# bombclock_1_3.net
KiCad netlist of a schematic drawn in EAGLE
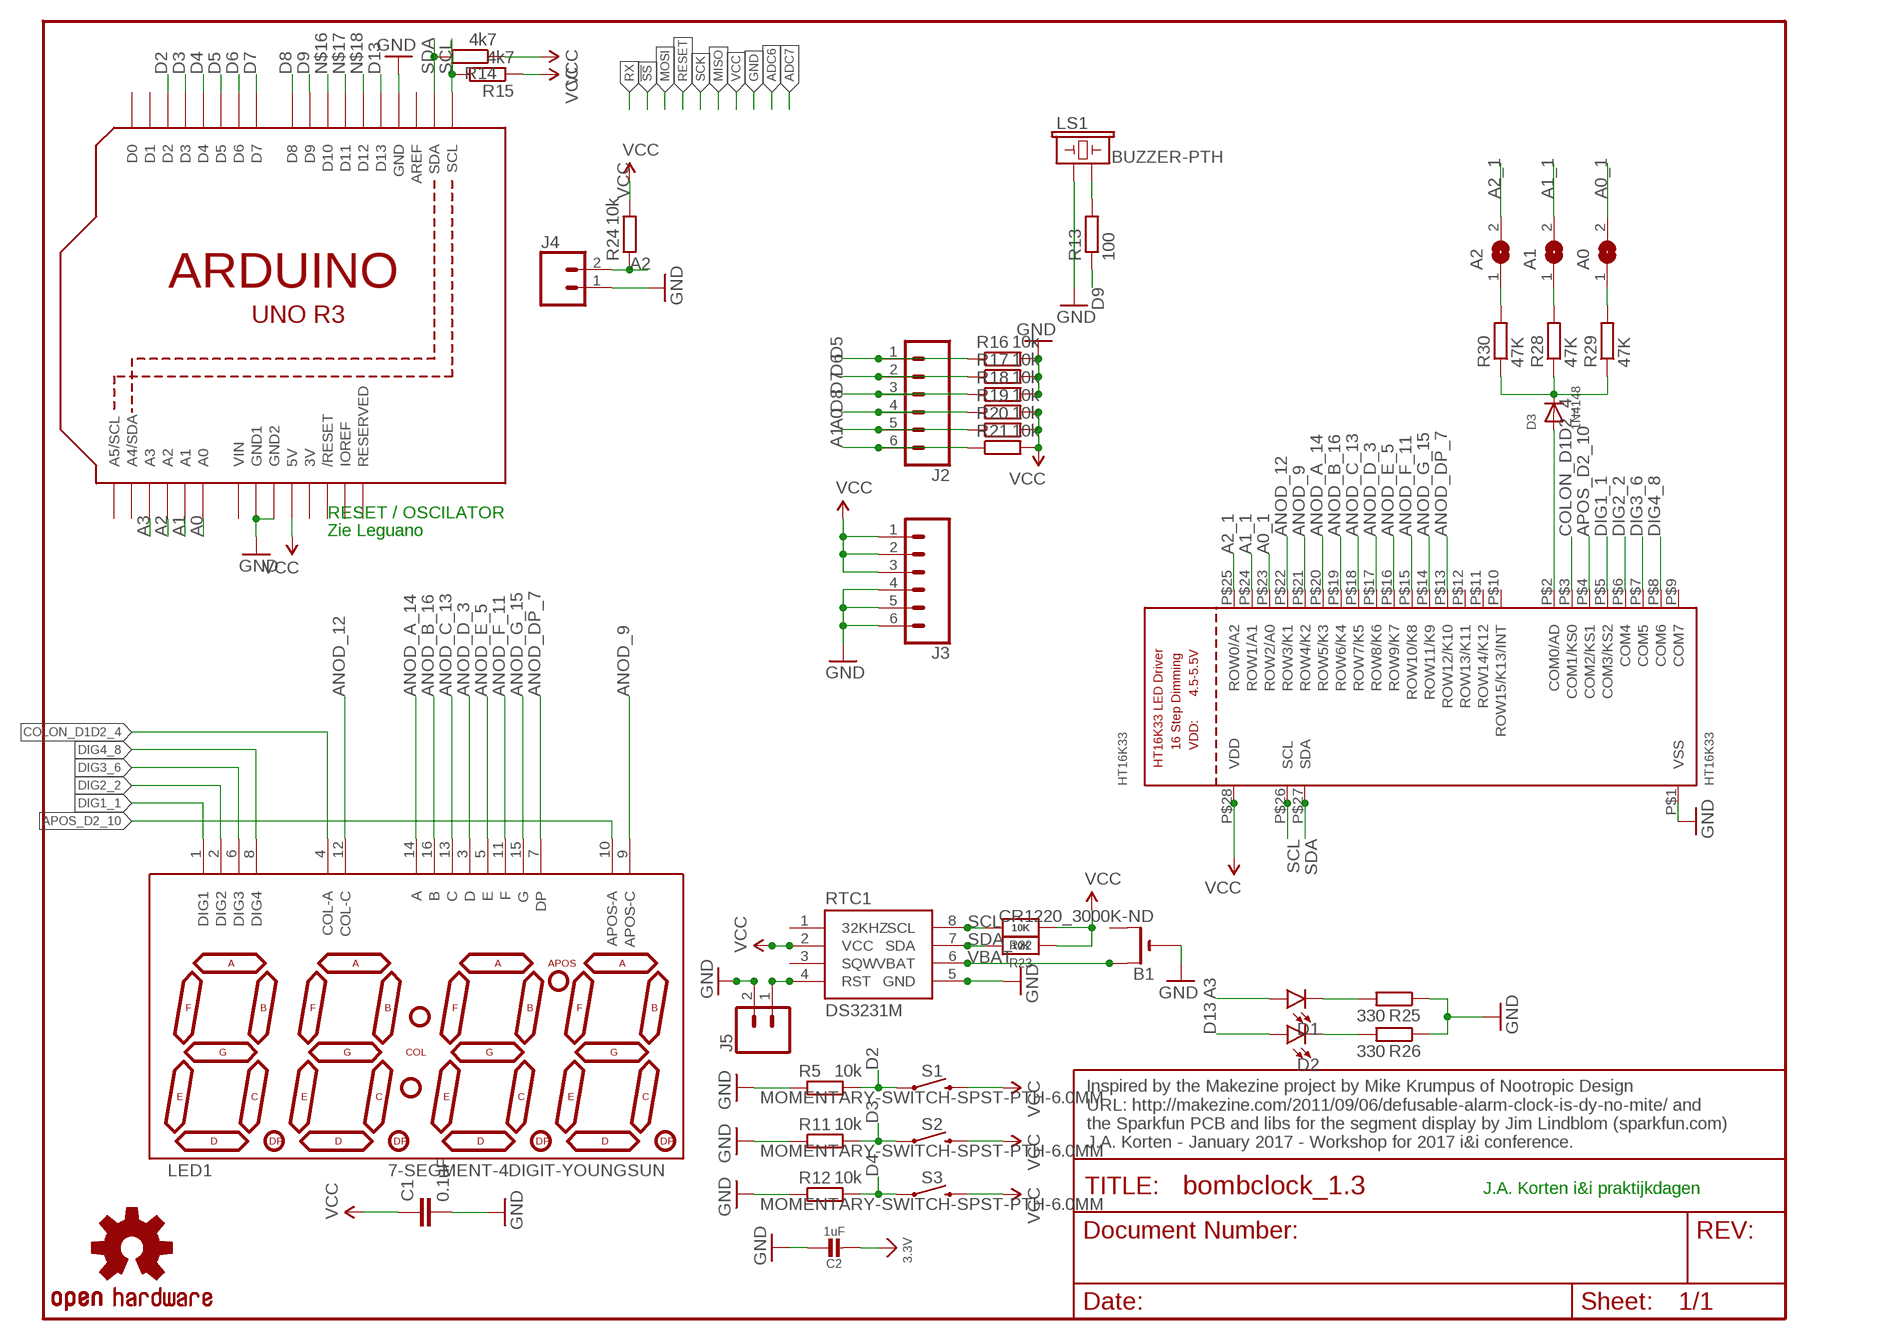
[diagram p0: schematic, sheet 1]

(export (version "E")
  (design (tool "Eeschema 10.0.6"))
  (components
    (comp (ref "A0")
      (value "SOLDERJUMPERREFLOW_NOPASTE")
      (footprint "eagle-import:SOLDERJUMPER_REFLOW_NOPASTE")
      (libsource (lib "eagle-import") (part "SOLDERJUMPERREFLOW_NOPASTE"))
    )
    (comp (ref "A1")
      (value "SOLDERJUMPERREFLOW_NOPASTE")
      (footprint "eagle-import:SOLDERJUMPER_REFLOW_NOPASTE")
      (libsource (lib "eagle-import") (part "SOLDERJUMPERREFLOW_NOPASTE"))
    )
    (comp (ref "A2")
      (value "SOLDERJUMPERREFLOW_NOPASTE")
      (footprint "eagle-import:SOLDERJUMPER_REFLOW_NOPASTE")
      (libsource (lib "eagle-import") (part "SOLDERJUMPERREFLOW_NOPASTE"))
    )
    (comp (ref "B1")
      (value "CR1220_3000K-ND")
      (footprint "eagle-import:CR1220-SMD")
      (libsource (lib "eagle-import") (part "CR1220SMT"))
    )
    (comp (ref "C1")
      (value "0.1uF")
      (footprint "eagle-import:0402-CAP")
      (libsource (lib "eagle-import") (part "CAP0402-CAP"))
    )
    (comp (ref "C2")
      (value "1uF")
      (footprint "eagle-import:0805-NO")
      (libsource (lib "eagle-import") (part "CAP_CERAMIC0805-NOOUTLINE"))
    )
    (comp (ref "D1")
      (value "LED5MM")
      (footprint "eagle-import:LED_5MM")
      (libsource (lib "eagle-import") (part "LED5MM"))
    )
    (comp (ref "D2")
      (value "LED5MM")
      (footprint "eagle-import:LED_5MM")
      (libsource (lib "eagle-import") (part "LED5MM"))
    )
    (comp (ref "D3")
      (value "1N4148")
      (footprint "eagle-import:SOD-323F")
      (libsource (lib "eagle-import") (part "DIODESOD-323F"))
    )
    (comp (ref "HT16K33")
      (value "HT16K33")
      (footprint "eagle-import:SOP28_300MIL")
      (libsource (lib "eagle-import") (part "HT16K33_SOP28"))
    )
    (comp (ref "J2")
      (value "CONN_06SILK_FEMALE_PTH")
      (footprint "eagle-import:1X06")
      (libsource (lib "eagle-import") (part "CONN_06SILK_FEMALE_PTH"))
    )
    (comp (ref "J3")
      (value "CONN_06SILK_FEMALE_PTH")
      (footprint "eagle-import:1X06")
      (libsource (lib "eagle-import") (part "CONN_06SILK_FEMALE_PTH"))
    )
    (comp (ref "J4")
      (value "CONN_02")
      (footprint "eagle-import:1X02")
      (libsource (lib "eagle-import") (part "CONN_02"))
    )
    (comp (ref "J5")
      (value "CONN_02")
      (footprint "eagle-import:1X02")
      (libsource (lib "eagle-import") (part "CONN_02"))
    )
    (comp (ref "LED1")
      (value "7-SEGMENT-4DIGIT-YOUNGSUN")
      (footprint "eagle-import:7-SEGMENT-4DIGIT-YOUNGSUN")
      (libsource (lib "eagle-import") (part "7-SEGMENT-4DIGIT-YOUNGSUN"))
    )
    (comp (ref "LS1")
      (value "BUZZER-PTH")
      (footprint "eagle-import:BUZZER-12MM")
      (libsource (lib "eagle-import") (part "BUZZER-PTH"))
    )
    (comp (ref "R5")
      (value "10k")
      (footprint "eagle-import:R0603")
      (libsource (lib "eagle-import") (part "R-EU_R0603"))
    )
    (comp (ref "R11")
      (value "10k")
      (footprint "eagle-import:R0603")
      (libsource (lib "eagle-import") (part "R-EU_R0603"))
    )
    (comp (ref "R12")
      (value "10k")
      (footprint "eagle-import:R0603")
      (libsource (lib "eagle-import") (part "R-EU_R0603"))
    )
    (comp (ref "R13")
      (value "100")
      (footprint "eagle-import:R0603")
      (libsource (lib "eagle-import") (part "R-EU_R0603"))
    )
    (comp (ref "R14")
      (value "4k7")
      (footprint "eagle-import:R0603")
      (libsource (lib "eagle-import") (part "R-EU_R0603"))
    )
    (comp (ref "R15")
      (value "4k7")
      (footprint "eagle-import:R0603")
      (libsource (lib "eagle-import") (part "R-EU_R0603"))
    )
    (comp (ref "R16")
      (value "10k")
      (footprint "eagle-import:R0603")
      (libsource (lib "eagle-import") (part "R-EU_R0603"))
    )
    (comp (ref "R17")
      (value "10k")
      (footprint "eagle-import:R0603")
      (libsource (lib "eagle-import") (part "R-EU_R0603"))
    )
    (comp (ref "R18")
      (value "10k")
      (footprint "eagle-import:R0603")
      (libsource (lib "eagle-import") (part "R-EU_R0603"))
    )
    (comp (ref "R19")
      (value "10k")
      (footprint "eagle-import:R0603")
      (libsource (lib "eagle-import") (part "R-EU_R0603"))
    )
    (comp (ref "R20")
      (value "10k")
      (footprint "eagle-import:R0603")
      (libsource (lib "eagle-import") (part "R-EU_R0603"))
    )
    (comp (ref "R21")
      (value "10k")
      (footprint "eagle-import:R0603")
      (libsource (lib "eagle-import") (part "R-EU_R0603"))
    )
    (comp (ref "R22")
      (value "10K")
      (footprint "eagle-import:0805-NO")
      (libsource (lib "eagle-import") (part "RESISTOR0805_NOOUTLINE"))
    )
    (comp (ref "R23")
      (value "10K")
      (footprint "eagle-import:0805-NO")
      (libsource (lib "eagle-import") (part "RESISTOR0805_NOOUTLINE"))
    )
    (comp (ref "R24")
      (value "10k")
      (footprint "eagle-import:R0603")
      (libsource (lib "eagle-import") (part "R-EU_R0603"))
    )
    (comp (ref "R25")
      (value "330")
      (footprint "eagle-import:R0603")
      (libsource (lib "eagle-import") (part "R-EU_R0603"))
    )
    (comp (ref "R26")
      (value "330")
      (footprint "eagle-import:R0603")
      (libsource (lib "eagle-import") (part "R-EU_R0603"))
    )
    (comp (ref "R28")
      (value "47K")
      (footprint "eagle-import:R0603")
      (libsource (lib "eagle-import") (part "resistor_R-EU_R0603"))
    )
    (comp (ref "R29")
      (value "47K")
      (footprint "eagle-import:R0603")
      (libsource (lib "eagle-import") (part "resistor_R-EU_R0603"))
    )
    (comp (ref "R30")
      (value "47K")
      (footprint "eagle-import:R0603")
      (libsource (lib "eagle-import") (part "resistor_R-EU_R0603"))
    )
    (comp (ref "RTC1")
      (value "DS3231M")
      (footprint "eagle-import:SO08")
      (libsource (lib "eagle-import") (part "DS3231M"))
    )
    (comp (ref "S1")
      (value "MOMENTARY-SWITCH-SPST-PTH-6.0MM")
      (footprint "eagle-import:TACTILE_SWITCH_PTH_6.0MM")
      (libsource (lib "eagle-import") (part "MOMENTARY-SWITCH-SPST-PTH-6.0MM"))
    )
    (comp (ref "S2")
      (value "MOMENTARY-SWITCH-SPST-PTH-6.0MM")
      (footprint "eagle-import:TACTILE_SWITCH_PTH_6.0MM")
      (libsource (lib "eagle-import") (part "MOMENTARY-SWITCH-SPST-PTH-6.0MM"))
    )
    (comp (ref "S3")
      (value "MOMENTARY-SWITCH-SPST-PTH-6.0MM")
      (footprint "eagle-import:TACTILE_SWITCH_PTH_6.0MM")
      (libsource (lib "eagle-import") (part "MOMENTARY-SWITCH-SPST-PTH-6.0MM"))
    )
    (comp (ref "U$4")
      (value "OSHW-LOGOS")
      (footprint "eagle-import:OSHW-LOGO-S")
      (libsource (lib "eagle-import") (part "OSHW-LOGOS"))
    )
    (comp (ref "U1")
      (value "ARDUINOR3-DIMENSION")
      (footprint "eagle-import:ARDUINOR3")
      (libsource (lib "eagle-import") (part "ARDUINOR3-DIMENSION"))
    )
  )
  (nets
    (net (code "1") (name "/3V") (class "Default")
      (node (ref "U1") (pin "3V") (pinfunction "3V_3V") (pintype "power_in"))
    )
    (net (code "2") (name "/A0") (class "Default")
      (node (ref "J2") (pin "5") (pinfunction "5_5") (pintype "passive"))
      (node (ref "R20") (pin "1") (pinfunction "1_1") (pintype "passive"))
      (node (ref "U1") (pin "A0") (pinfunction "A0_A0") (pintype "bidirectional"))
    )
    (net (code "3") (name "/A0_1") (class "Default")
      (node (ref "A0") (pin "2") (pinfunction "2_2") (pintype "passive"))
      (node (ref "HT16K33") (pin "P$23") (pinfunction "ROW2/A0_P$23") (pintype "bidirectional"))
    )
    (net (code "4") (name "/A1") (class "Default")
      (node (ref "J2") (pin "6") (pinfunction "6_6") (pintype "passive"))
      (node (ref "R21") (pin "1") (pinfunction "1_1") (pintype "passive"))
      (node (ref "U1") (pin "A1") (pinfunction "A1_A1") (pintype "bidirectional"))
    )
    (net (code "5") (name "/A1_1") (class "Default")
      (node (ref "A1") (pin "2") (pinfunction "2_2") (pintype "passive"))
      (node (ref "HT16K33") (pin "P$24") (pinfunction "ROW1/A1_P$24") (pintype "bidirectional"))
    )
    (net (code "6") (name "/A2") (class "Default")
      (node (ref "J4") (pin "2") (pinfunction "2_2") (pintype "passive"))
      (node (ref "R24") (pin "1") (pinfunction "1_1") (pintype "passive"))
      (node (ref "U1") (pin "A2") (pinfunction "A2_A2") (pintype "bidirectional"))
    )
    (net (code "7") (name "/A2_1") (class "Default")
      (node (ref "A2") (pin "2") (pinfunction "2_2") (pintype "passive"))
      (node (ref "HT16K33") (pin "P$25") (pinfunction "ROW0/A2_P$25") (pintype "bidirectional"))
    )
    (net (code "8") (name "/A3") (class "Default")
      (node (ref "D1") (pin "A") (pinfunction "A_A") (pintype "passive"))
      (node (ref "U1") (pin "A3") (pinfunction "A3_A3") (pintype "bidirectional"))
    )
    (net (code "9") (name "/ANOD_9") (class "Default")
      (node (ref "HT16K33") (pin "P$21") (pinfunction "ROW4/K2_P$21") (pintype "bidirectional"))
      (node (ref "LED1") (pin "9") (pinfunction "APOS-C_9") (pintype "bidirectional"))
    )
    (net (code "10") (name "/ANOD_12") (class "Default")
      (node (ref "HT16K33") (pin "P$22") (pinfunction "ROW3/K1_P$22") (pintype "bidirectional"))
      (node (ref "LED1") (pin "12") (pinfunction "COL-C_12") (pintype "bidirectional"))
    )
    (net (code "11") (name "/ANOD_A_14") (class "Default")
      (node (ref "HT16K33") (pin "P$20") (pinfunction "ROW5/K3_P$20") (pintype "bidirectional"))
      (node (ref "LED1") (pin "14") (pinfunction "A_14") (pintype "bidirectional"))
    )
    (net (code "12") (name "/ANOD_B_16") (class "Default")
      (node (ref "HT16K33") (pin "P$19") (pinfunction "ROW6/K4_P$19") (pintype "bidirectional"))
      (node (ref "LED1") (pin "16") (pinfunction "B_16") (pintype "bidirectional"))
    )
    (net (code "13") (name "/ANOD_C_13") (class "Default")
      (node (ref "HT16K33") (pin "P$18") (pinfunction "ROW7/K5_P$18") (pintype "bidirectional"))
      (node (ref "LED1") (pin "13") (pinfunction "C_13") (pintype "bidirectional"))
    )
    (net (code "14") (name "/ANOD_DP_7") (class "Default")
      (node (ref "HT16K33") (pin "P$13") (pinfunction "ROW12/K10_P$13") (pintype "bidirectional"))
      (node (ref "LED1") (pin "7") (pinfunction "DP_7") (pintype "bidirectional"))
    )
    (net (code "15") (name "/ANOD_D_3") (class "Default")
      (node (ref "HT16K33") (pin "P$17") (pinfunction "ROW8/K6_P$17") (pintype "bidirectional"))
      (node (ref "LED1") (pin "3") (pinfunction "D_3") (pintype "bidirectional"))
    )
    (net (code "16") (name "/ANOD_E_5") (class "Default")
      (node (ref "HT16K33") (pin "P$16") (pinfunction "ROW9/K7_P$16") (pintype "bidirectional"))
      (node (ref "LED1") (pin "5") (pinfunction "E_5") (pintype "bidirectional"))
    )
    (net (code "17") (name "/ANOD_F_11") (class "Default")
      (node (ref "HT16K33") (pin "P$15") (pinfunction "ROW10/K8_P$15") (pintype "bidirectional"))
      (node (ref "LED1") (pin "11") (pinfunction "F_11") (pintype "bidirectional"))
    )
    (net (code "18") (name "/ANOD_G_15") (class "Default")
      (node (ref "HT16K33") (pin "P$14") (pinfunction "ROW11/K9_P$14") (pintype "bidirectional"))
      (node (ref "LED1") (pin "15") (pinfunction "G_15") (pintype "bidirectional"))
    )
    (net (code "19") (name "/D2") (class "Default")
      (node (ref "R5") (pin "2") (pinfunction "2_2") (pintype "passive"))
      (node (ref "S1") (pin "1") (pinfunction "1_1") (pintype "passive"))
      (node (ref "U1") (pin "D2") (pinfunction "D2_D2") (pintype "bidirectional"))
    )
    (net (code "20") (name "/D3") (class "Default")
      (node (ref "R11") (pin "2") (pinfunction "2_2") (pintype "passive"))
      (node (ref "S2") (pin "1") (pinfunction "1_1") (pintype "passive"))
      (node (ref "U1") (pin "D3") (pinfunction "D3_D3") (pintype "bidirectional"))
    )
    (net (code "21") (name "/D4") (class "Default")
      (node (ref "R12") (pin "2") (pinfunction "2_2") (pintype "passive"))
      (node (ref "S3") (pin "1") (pinfunction "1_1") (pintype "passive"))
      (node (ref "U1") (pin "D4") (pinfunction "D4_D4") (pintype "bidirectional"))
    )
    (net (code "22") (name "/D5") (class "Default")
      (node (ref "J2") (pin "1") (pinfunction "1_1") (pintype "passive"))
      (node (ref "R16") (pin "1") (pinfunction "1_1") (pintype "passive"))
      (node (ref "U1") (pin "D5") (pinfunction "D5_D5") (pintype "bidirectional"))
    )
    (net (code "23") (name "/D6") (class "Default")
      (node (ref "J2") (pin "2") (pinfunction "2_2") (pintype "passive"))
      (node (ref "R17") (pin "1") (pinfunction "1_1") (pintype "passive"))
      (node (ref "U1") (pin "D6") (pinfunction "D6_D6") (pintype "bidirectional"))
    )
    (net (code "24") (name "/D7") (class "Default")
      (node (ref "J2") (pin "3") (pinfunction "3_3") (pintype "passive"))
      (node (ref "R18") (pin "1") (pinfunction "1_1") (pintype "passive"))
      (node (ref "U1") (pin "D7") (pinfunction "D7_D7") (pintype "bidirectional"))
    )
    (net (code "25") (name "/D8") (class "Default")
      (node (ref "J2") (pin "4") (pinfunction "4_4") (pintype "passive"))
      (node (ref "R19") (pin "1") (pinfunction "1_1") (pintype "passive"))
      (node (ref "U1") (pin "D8") (pinfunction "D8_D8") (pintype "bidirectional"))
    )
    (net (code "26") (name "/D9") (class "Default")
      (node (ref "R13") (pin "1") (pinfunction "1_1") (pintype "passive"))
      (node (ref "U1") (pin "D9") (pinfunction "D9_D9") (pintype "bidirectional"))
    )
    (net (code "27") (name "/D13") (class "Default")
      (node (ref "D2") (pin "A") (pinfunction "A_A") (pintype "passive"))
      (node (ref "U1") (pin "D13") (pinfunction "D13_D13") (pintype "bidirectional"))
    )
    (net (code "28") (name "/N$16") (class "Default")
      (node (ref "U1") (pin "D10") (pinfunction "D10_D10") (pintype "bidirectional"))
    )
    (net (code "29") (name "/N$17") (class "Default")
      (node (ref "U1") (pin "D11") (pinfunction "D11_D11") (pintype "bidirectional"))
    )
    (net (code "30") (name "/N$18") (class "Default")
      (node (ref "U1") (pin "D12") (pinfunction "D12_D12") (pintype "bidirectional"))
    )
    (net (code "31") (name "/SCL") (class "Default")
      (node (ref "HT16K33") (pin "P$26") (pinfunction "SCL_P$26") (pintype "bidirectional"))
      (node (ref "R15") (pin "2") (pinfunction "2_2") (pintype "passive"))
      (node (ref "R22") (pin "2") (pinfunction "2_2") (pintype "passive"))
      (node (ref "RTC1") (pin "8") (pinfunction "SCL_8") (pintype "bidirectional"))
      (node (ref "U1") (pin "SCL") (pinfunction "SCL_SCL") (pintype "bidirectional"))
    )
    (net (code "32") (name "/SDA") (class "Default")
      (node (ref "HT16K33") (pin "P$27") (pinfunction "SDA_P$27") (pintype "bidirectional"))
      (node (ref "R14") (pin "2") (pinfunction "2_2") (pintype "passive"))
      (node (ref "R23") (pin "2") (pinfunction "2_2") (pintype "passive"))
      (node (ref "RTC1") (pin "7") (pinfunction "SDA_7") (pintype "bidirectional"))
      (node (ref "U1") (pin "SDA") (pinfunction "SDA_SDA") (pintype "bidirectional"))
    )
    (net (code "33") (name "/VBAT") (class "Default")
      (node (ref "B1") (pin "+$1") (pinfunction "+_+$1") (pintype "passive"))
      (node (ref "RTC1") (pin "6") (pinfunction "VBAT_6") (pintype "power_in"))
    )
    (net (code "34") (name "/VIN") (class "Default")
      (node (ref "U1") (pin "VIN") (pinfunction "VIN_VIN") (pintype "power_in"))
    )
    (net (code "36") (name "3.3V") (class "Default")
      (node (ref "C2") (pin "2") (pinfunction "2_2") (pintype "passive"))
    )
    (net (code "39") (name "APOS_D2_10") (class "Default")
      (node (ref "HT16K33") (pin "P$4") (pinfunction "COM2/KS1_P$4") (pintype "bidirectional"))
      (node (ref "LED1") (pin "10") (pinfunction "APOS-A_10") (pintype "bidirectional"))
    )
    (net (code "40") (name "COLON_D1D2_4") (class "Default")
      (node (ref "HT16K33") (pin "P$3") (pinfunction "COM1/KS0_P$3") (pintype "bidirectional"))
      (node (ref "LED1") (pin "4") (pinfunction "COL-A_4") (pintype "bidirectional"))
    )
    (net (code "41") (name "DIG1_1") (class "Default")
      (node (ref "HT16K33") (pin "P$5") (pinfunction "COM3/KS2_P$5") (pintype "bidirectional"))
      (node (ref "LED1") (pin "1") (pinfunction "DIG1_1") (pintype "bidirectional"))
    )
    (net (code "42") (name "DIG2_2") (class "Default")
      (node (ref "HT16K33") (pin "P$6") (pinfunction "COM4_P$6") (pintype "bidirectional"))
      (node (ref "LED1") (pin "2") (pinfunction "DIG2_2") (pintype "bidirectional"))
    )
    (net (code "43") (name "DIG3_6") (class "Default")
      (node (ref "HT16K33") (pin "P$7") (pinfunction "COM5_P$7") (pintype "bidirectional"))
      (node (ref "LED1") (pin "6") (pinfunction "DIG3_6") (pintype "bidirectional"))
    )
    (net (code "44") (name "DIG4_8") (class "Default")
      (node (ref "HT16K33") (pin "P$8") (pinfunction "COM6_P$8") (pintype "bidirectional"))
      (node (ref "LED1") (pin "8") (pinfunction "DIG4_8") (pintype "bidirectional"))
    )
    (net (code "45") (name "GND") (class "Default")
      (node (ref "B1") (pin "-") (pinfunction "-_-") (pintype "passive"))
      (node (ref "C1") (pin "2") (pinfunction "2_2") (pintype "passive"))
      (node (ref "C2") (pin "1") (pinfunction "1_1") (pintype "passive"))
      (node (ref "HT16K33") (pin "P$1") (pinfunction "VSS_P$1") (pintype "bidirectional"))
      (node (ref "J3") (pin "4") (pinfunction "4_4") (pintype "passive"))
      (node (ref "J3") (pin "5") (pinfunction "5_5") (pintype "passive"))
      (node (ref "J3") (pin "6") (pinfunction "6_6") (pintype "passive"))
      (node (ref "J4") (pin "1") (pinfunction "1_1") (pintype "passive"))
      (node (ref "J5") (pin "2") (pinfunction "2_2") (pintype "passive"))
      (node (ref "LS1") (pin "+") (pinfunction "1_+") (pintype "passive"))
      (node (ref "R11") (pin "1") (pinfunction "1_1") (pintype "passive"))
      (node (ref "R12") (pin "1") (pinfunction "1_1") (pintype "passive"))
      (node (ref "R16") (pin "2") (pinfunction "2_2") (pintype "passive"))
      (node (ref "R17") (pin "2") (pinfunction "2_2") (pintype "passive"))
      (node (ref "R18") (pin "2") (pinfunction "2_2") (pintype "passive"))
      (node (ref "R25") (pin "1") (pinfunction "1_1") (pintype "passive"))
      (node (ref "R26") (pin "1") (pinfunction "1_1") (pintype "passive"))
      (node (ref "R5") (pin "1") (pinfunction "1_1") (pintype "passive"))
      (node (ref "RTC1") (pin "5") (pinfunction "GND_5") (pintype "power_in"))
      (node (ref "U1") (pin "GND") (pinfunction "GND_GND") (pintype "power_in"))
      (node (ref "U1") (pin "GND1") (pinfunction "GND1_GND1") (pintype "power_in"))
      (node (ref "U1") (pin "GND2") (pinfunction "GND2_GND2") (pintype "power_in"))
    )
    (net (code "48") (name "Net-(A0-Pad1)") (class "Default")
      (node (ref "A0") (pin "1") (pinfunction "1_1") (pintype "passive"))
      (node (ref "R29") (pin "2") (pinfunction "2_2") (pintype "passive"))
    )
    (net (code "49") (name "Net-(A1-Pad1)") (class "Default")
      (node (ref "A1") (pin "1") (pinfunction "1_1") (pintype "passive"))
      (node (ref "R28") (pin "2") (pinfunction "2_2") (pintype "passive"))
    )
    (net (code "50") (name "Net-(A2-Pad1)") (class "Default")
      (node (ref "A2") (pin "1") (pinfunction "1_1") (pintype "passive"))
      (node (ref "R30") (pin "2") (pinfunction "2_2") (pintype "passive"))
    )
    (net (code "51") (name "Net-(D1-C)") (class "Default")
      (node (ref "D1") (pin "K") (pinfunction "C_K") (pintype "passive"))
      (node (ref "R25") (pin "2") (pinfunction "2_2") (pintype "passive"))
    )
    (net (code "52") (name "Net-(D2-C)") (class "Default")
      (node (ref "D2") (pin "K") (pinfunction "C_K") (pintype "passive"))
      (node (ref "R26") (pin "2") (pinfunction "2_2") (pintype "passive"))
    )
    (net (code "53") (name "Net-(D3-PadC)") (class "Default")
      (node (ref "D3") (pin "C") (pinfunction "C_C") (pintype "passive"))
      (node (ref "R28") (pin "1") (pinfunction "1_1") (pintype "passive"))
      (node (ref "R29") (pin "1") (pinfunction "1_1") (pintype "passive"))
      (node (ref "R30") (pin "1") (pinfunction "1_1") (pintype "passive"))
    )
    (net (code "54") (name "Net-(HT16K33-COM0{slash}AD)") (class "Default")
      (node (ref "D3") (pin "A") (pinfunction "A_A") (pintype "passive"))
      (node (ref "HT16K33") (pin "P$2") (pinfunction "COM0/AD_P$2") (pintype "bidirectional"))
    )
    (net (code "55") (name "Net-(LS1-2)") (class "Default")
      (node (ref "LS1") (pin "-") (pinfunction "2_-") (pintype "passive"))
      (node (ref "R13") (pin "2") (pinfunction "2_2") (pintype "passive"))
    )
    (net (code "56") (name "Net-(RTC1-RST)") (class "Default")
      (node (ref "J5") (pin "1") (pinfunction "1_1") (pintype "passive"))
      (node (ref "RTC1") (pin "4") (pinfunction "RST_4") (pintype "bidirectional"))
    )
    (net (code "60") (name "VCC") (class "Default")
      (node (ref "C1") (pin "1") (pinfunction "1_1") (pintype "passive"))
      (node (ref "HT16K33") (pin "P$28") (pinfunction "VDD_P$28") (pintype "bidirectional"))
      (node (ref "J3") (pin "1") (pinfunction "1_1") (pintype "passive"))
      (node (ref "J3") (pin "2") (pinfunction "2_2") (pintype "passive"))
      (node (ref "J3") (pin "3") (pinfunction "3_3") (pintype "passive"))
      (node (ref "R14") (pin "1") (pinfunction "1_1") (pintype "passive"))
      (node (ref "R15") (pin "1") (pinfunction "1_1") (pintype "passive"))
      (node (ref "R19") (pin "2") (pinfunction "2_2") (pintype "passive"))
      (node (ref "R20") (pin "2") (pinfunction "2_2") (pintype "passive"))
      (node (ref "R21") (pin "2") (pinfunction "2_2") (pintype "passive"))
      (node (ref "R22") (pin "1") (pinfunction "1_1") (pintype "passive"))
      (node (ref "R23") (pin "1") (pinfunction "1_1") (pintype "passive"))
      (node (ref "R24") (pin "2") (pinfunction "2_2") (pintype "passive"))
      (node (ref "RTC1") (pin "2") (pinfunction "VCC_2") (pintype "power_in"))
      (node (ref "S1") (pin "3") (pinfunction "2_3") (pintype "passive"))
      (node (ref "S2") (pin "3") (pinfunction "2_3") (pintype "passive"))
      (node (ref "S3") (pin "3") (pinfunction "2_3") (pintype "passive"))
      (node (ref "U1") (pin "5V") (pinfunction "5V_5V") (pintype "power_in"))
    )
    (net (code "61") (name "unconnected-(B1-+1-Pad+$2)") (class "Default")
      (node (ref "B1") (pin "+$2") (pinfunction "+1_+$2") (pintype "passive"))
    )
    (net (code "62") (name "unconnected-(HT16K33-COM7-PadP$9)") (class "Default")
      (node (ref "HT16K33") (pin "P$9") (pinfunction "COM7_P$9") (pintype "bidirectional"))
    )
    (net (code "63") (name "unconnected-(HT16K33-ROW13{slash}K11-PadP$12)") (class "Default")
      (node (ref "HT16K33") (pin "P$12") (pinfunction "ROW13/K11_P$12") (pintype "bidirectional"))
    )
    (net (code "64") (name "unconnected-(HT16K33-ROW14{slash}K12-PadP$11)") (class "Default")
      (node (ref "HT16K33") (pin "P$11") (pinfunction "ROW14/K12_P$11") (pintype "bidirectional"))
    )
    (net (code "65") (name "unconnected-(HT16K33-ROW15{slash}K13{slash}INT-PadP$10)") (class "Default")
      (node (ref "HT16K33") (pin "P$10") (pinfunction "ROW15/K13/INT_P$10") (pintype "bidirectional"))
    )
    (net (code "66") (name "unconnected-(RTC1-32KHZ-Pad1)") (class "Default")
      (node (ref "RTC1") (pin "1") (pinfunction "32KHZ_1") (pintype "output"))
    )
    (net (code "67") (name "unconnected-(RTC1-SQW-Pad3)") (class "Default")
      (node (ref "RTC1") (pin "3") (pinfunction "SQW_3") (pintype "output"))
    )
    (net (code "68") (name "unconnected-(U1-A4{slash}SDA-PadA4)") (class "Default")
      (node (ref "U1") (pin "A4") (pinfunction "A4/SDA_A4") (pintype "bidirectional"))
    )
    (net (code "69") (name "unconnected-(U1-A5{slash}SCL-PadA5)") (class "Default")
      (node (ref "U1") (pin "A5") (pinfunction "A5/SCL_A5") (pintype "bidirectional"))
    )
    (net (code "70") (name "unconnected-(U1-PadAREF)") (class "Default")
      (node (ref "U1") (pin "AREF") (pinfunction "AREF_AREF") (pintype "bidirectional"))
    )
    (net (code "71") (name "unconnected-(U1-PadD0)") (class "Default")
      (node (ref "U1") (pin "D0") (pinfunction "D0_D0") (pintype "bidirectional"))
    )
    (net (code "72") (name "unconnected-(U1-PadD1)") (class "Default")
      (node (ref "U1") (pin "D1") (pinfunction "D1_D1") (pintype "bidirectional"))
    )
    (net (code "73") (name "unconnected-(U1-PadIOREF)") (class "Default")
      (node (ref "U1") (pin "IOREF") (pinfunction "IOREF_IOREF") (pintype "output"))
    )
    (net (code "74") (name "unconnected-(U1-PadRESERVED)") (class "Default")
      (node (ref "U1") (pin "RESERVED") (pinfunction "RESERVED_RESERVED") (pintype "no_connect"))
    )
    (net (code "75") (name "unconnected-(U1-{slash}RESET-PadRESET)") (class "Default")
      (node (ref "U1") (pin "RESET") (pinfunction "/RESET_RESET") (pintype "bidirectional"))
    )
  )
)
